# BeagleBoneBlack_cape_template.net
KiCad netlist of a schematic drawn in Altium Designer
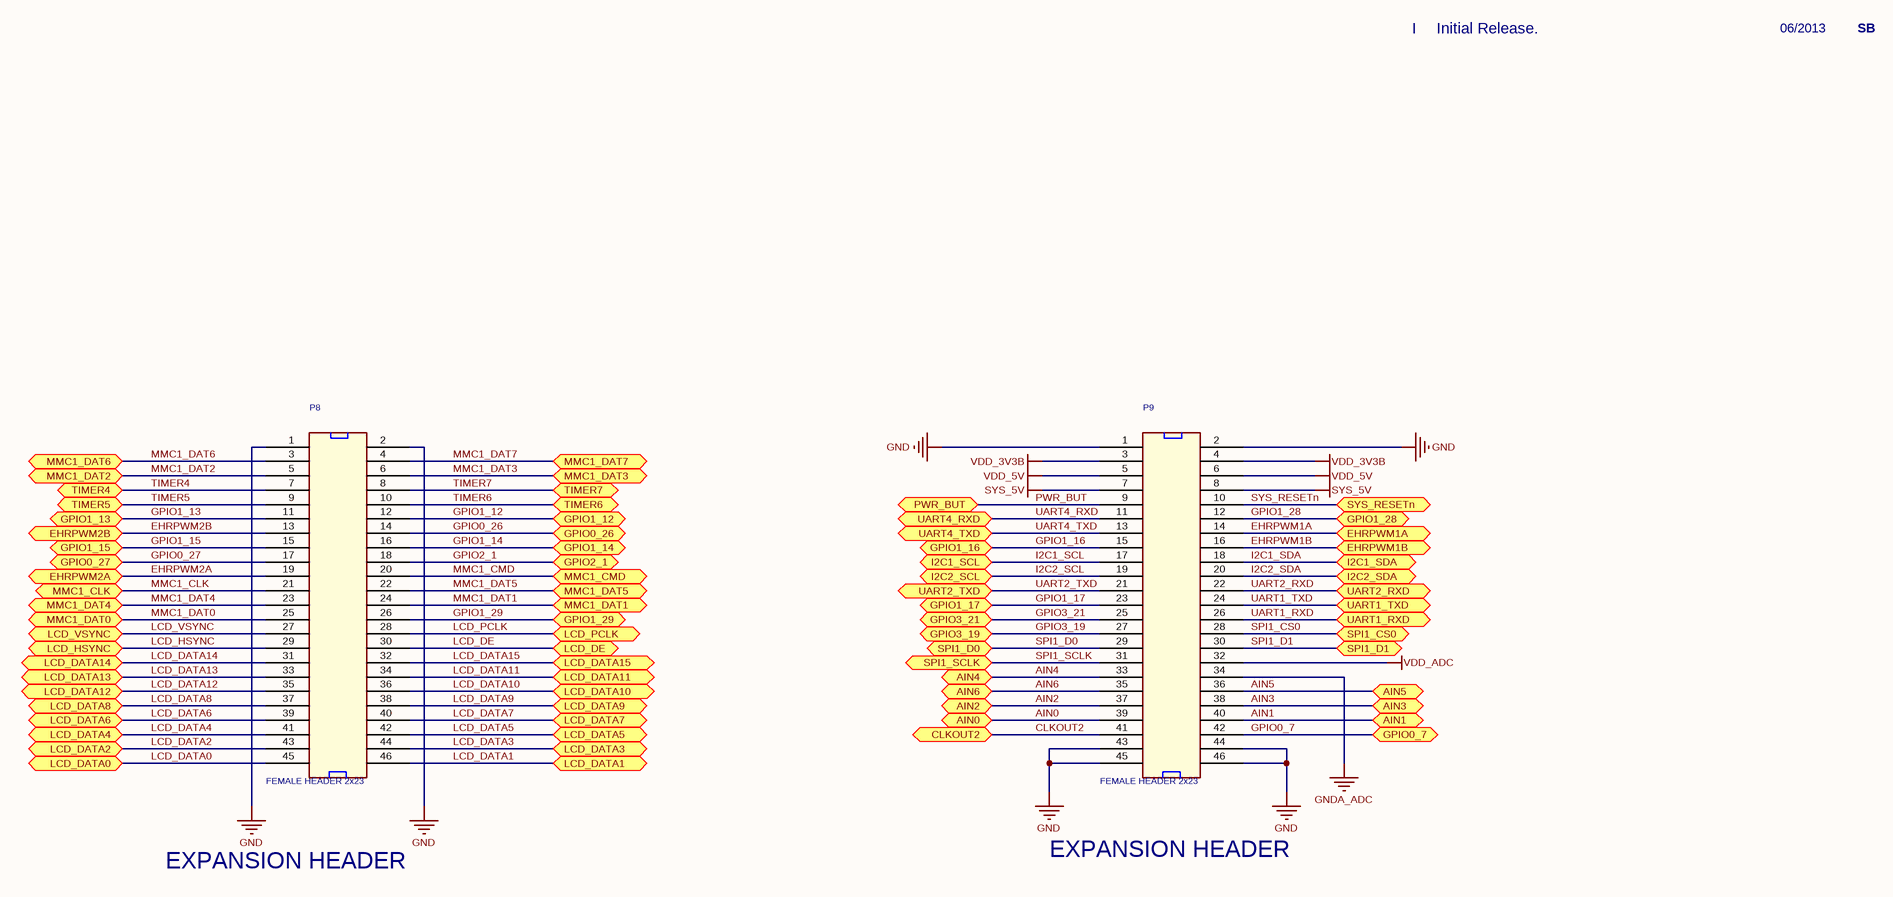
[diagram p0: BeagleBoneBlack_cape_template.SchDoc]

(export (version "E")
  (design (tool "Eeschema 10.0.6"))
  (components
    (comp (ref "P8")
      (value "FEMALE HEADER 2x23")
      (description "CONN HEADER FMAL 46PS.1\" DL GOLD")
      (fields
        (field (name "MANUFACTURER") "Sullins Connector Solutions")
        (field (name "MANUFACTURER PART NUMBER") "PPPC232LFBN-RC")
      )
      (libsource (lib "BEAGLEBONEBLACK_REV A5B") (part "HDR_46_F_2_0.1_0.1"))
    )
    (comp (ref "P9")
      (value "FEMALE HEADER 2x23")
      (description "CONN HEADER FMAL 46PS.1\" DL GOLD")
      (fields
        (field (name "MANUFACTURER") "Sullins Connector Solutions")
        (field (name "MANUFACTURER PART NUMBER") "PPPC232LFBN-RC")
      )
      (libsource (lib "BEAGLEBONEBLACK_REV A5B") (part "HDR_46_F_2_0.1_0.1"))
    )
  )
  (nets
    (net (code "1") (name "/AIN0") (class "Default")
      (node (ref "P9") (pin "39") (pinfunction "20_39") (pintype "passive"))
    )
    (net (code "2") (name "/AIN1") (class "Default")
      (node (ref "P9") (pin "40") (pinfunction "45_40") (pintype "passive"))
    )
    (net (code "3") (name "/AIN2") (class "Default")
      (node (ref "P9") (pin "37") (pinfunction "19_37") (pintype "passive"))
    )
    (net (code "4") (name "/AIN3") (class "Default")
      (node (ref "P9") (pin "38") (pinfunction "44_38") (pintype "passive"))
    )
    (net (code "5") (name "/AIN4") (class "Default")
      (node (ref "P9") (pin "33") (pinfunction "17_33") (pintype "passive"))
    )
    (net (code "6") (name "/AIN5") (class "Default")
      (node (ref "P9") (pin "36") (pinfunction "43_36") (pintype "passive"))
    )
    (net (code "7") (name "/AIN6") (class "Default")
      (node (ref "P9") (pin "35") (pinfunction "18_35") (pintype "passive"))
    )
    (net (code "8") (name "/CLKOUT2") (class "Default")
      (node (ref "P9") (pin "41") (pinfunction "21_41") (pintype "passive"))
    )
    (net (code "9") (name "/EHRPWM1A") (class "Default")
      (node (ref "P9") (pin "14") (pinfunction "32_14") (pintype "passive"))
    )
    (net (code "10") (name "/EHRPWM1B") (class "Default")
      (node (ref "P9") (pin "16") (pinfunction "33_16") (pintype "passive"))
    )
    (net (code "11") (name "/EHRPWM2A") (class "Default")
      (node (ref "P8") (pin "19") (pinfunction "10_19") (pintype "passive"))
    )
    (net (code "12") (name "/EHRPWM2B") (class "Default")
      (node (ref "P8") (pin "13") (pinfunction "7_13") (pintype "passive"))
    )
    (net (code "13") (name "/GPIO0_7") (class "Default")
      (node (ref "P9") (pin "42") (pinfunction "46_42") (pintype "passive"))
    )
    (net (code "14") (name "/GPIO0_26") (class "Default")
      (node (ref "P8") (pin "14") (pinfunction "32_14") (pintype "passive"))
    )
    (net (code "15") (name "/GPIO0_27") (class "Default")
      (node (ref "P8") (pin "17") (pinfunction "9_17") (pintype "passive"))
    )
    (net (code "16") (name "/GPIO1_12") (class "Default")
      (node (ref "P8") (pin "12") (pinfunction "31_12") (pintype "passive"))
    )
    (net (code "17") (name "/GPIO1_13") (class "Default")
      (node (ref "P8") (pin "11") (pinfunction "6_11") (pintype "passive"))
    )
    (net (code "18") (name "/GPIO1_14") (class "Default")
      (node (ref "P8") (pin "16") (pinfunction "33_16") (pintype "passive"))
    )
    (net (code "19") (name "/GPIO1_15") (class "Default")
      (node (ref "P8") (pin "15") (pinfunction "8_15") (pintype "passive"))
    )
    (net (code "20") (name "/GPIO1_16") (class "Default")
      (node (ref "P9") (pin "15") (pinfunction "8_15") (pintype "passive"))
    )
    (net (code "21") (name "/GPIO1_17") (class "Default")
      (node (ref "P9") (pin "23") (pinfunction "12_23") (pintype "passive"))
    )
    (net (code "22") (name "/GPIO1_28") (class "Default")
      (node (ref "P9") (pin "12") (pinfunction "31_12") (pintype "passive"))
    )
    (net (code "23") (name "/GPIO1_29") (class "Default")
      (node (ref "P8") (pin "26") (pinfunction "38_26") (pintype "passive"))
    )
    (net (code "24") (name "/GPIO2_1") (class "Default")
      (node (ref "P8") (pin "18") (pinfunction "34_18") (pintype "passive"))
    )
    (net (code "25") (name "/GPIO3_19") (class "Default")
      (node (ref "P9") (pin "27") (pinfunction "14_27") (pintype "passive"))
    )
    (net (code "26") (name "/GPIO3_21") (class "Default")
      (node (ref "P9") (pin "25") (pinfunction "13_25") (pintype "passive"))
    )
    (net (code "27") (name "/I2C1_SCL") (class "Default")
      (node (ref "P9") (pin "17") (pinfunction "9_17") (pintype "passive"))
    )
    (net (code "28") (name "/I2C1_SDA") (class "Default")
      (node (ref "P9") (pin "18") (pinfunction "34_18") (pintype "passive"))
    )
    (net (code "29") (name "/I2C2_SCL") (class "Default")
      (node (ref "P9") (pin "19") (pinfunction "10_19") (pintype "passive"))
    )
    (net (code "30") (name "/I2C2_SDA") (class "Default")
      (node (ref "P9") (pin "20") (pinfunction "35_20") (pintype "passive"))
    )
    (net (code "31") (name "/LCD_DATA0") (class "Default")
      (node (ref "P8") (pin "45") (pinfunction "23_45") (pintype "passive"))
    )
    (net (code "32") (name "/LCD_DATA1") (class "Default")
      (node (ref "P8") (pin "46") (pinfunction "48_46") (pintype "passive"))
    )
    (net (code "33") (name "/LCD_DATA2") (class "Default")
      (node (ref "P8") (pin "43") (pinfunction "22_43") (pintype "passive"))
    )
    (net (code "34") (name "/LCD_DATA3") (class "Default")
      (node (ref "P8") (pin "44") (pinfunction "47_44") (pintype "passive"))
    )
    (net (code "35") (name "/LCD_DATA4") (class "Default")
      (node (ref "P8") (pin "41") (pinfunction "21_41") (pintype "passive"))
    )
    (net (code "36") (name "/LCD_DATA5") (class "Default")
      (node (ref "P8") (pin "42") (pinfunction "46_42") (pintype "passive"))
    )
    (net (code "37") (name "/LCD_DATA6") (class "Default")
      (node (ref "P8") (pin "39") (pinfunction "20_39") (pintype "passive"))
    )
    (net (code "38") (name "/LCD_DATA7") (class "Default")
      (node (ref "P8") (pin "40") (pinfunction "45_40") (pintype "passive"))
    )
    (net (code "39") (name "/LCD_DATA8") (class "Default")
      (node (ref "P8") (pin "37") (pinfunction "19_37") (pintype "passive"))
    )
    (net (code "40") (name "/LCD_DATA9") (class "Default")
      (node (ref "P8") (pin "38") (pinfunction "44_38") (pintype "passive"))
    )
    (net (code "41") (name "/LCD_DATA10") (class "Default")
      (node (ref "P8") (pin "36") (pinfunction "43_36") (pintype "passive"))
    )
    (net (code "42") (name "/LCD_DATA11") (class "Default")
      (node (ref "P8") (pin "34") (pinfunction "42_34") (pintype "passive"))
    )
    (net (code "43") (name "/LCD_DATA12") (class "Default")
      (node (ref "P8") (pin "35") (pinfunction "18_35") (pintype "passive"))
    )
    (net (code "44") (name "/LCD_DATA13") (class "Default")
      (node (ref "P8") (pin "33") (pinfunction "17_33") (pintype "passive"))
    )
    (net (code "45") (name "/LCD_DATA14") (class "Default")
      (node (ref "P8") (pin "31") (pinfunction "16_31") (pintype "passive"))
    )
    (net (code "46") (name "/LCD_DATA15") (class "Default")
      (node (ref "P8") (pin "32") (pinfunction "41_32") (pintype "passive"))
    )
    (net (code "47") (name "/LCD_DE") (class "Default")
      (node (ref "P8") (pin "30") (pinfunction "40_30") (pintype "passive"))
    )
    (net (code "48") (name "/LCD_HSYNC") (class "Default")
      (node (ref "P8") (pin "29") (pinfunction "15_29") (pintype "passive"))
    )
    (net (code "49") (name "/LCD_PCLK") (class "Default")
      (node (ref "P8") (pin "28") (pinfunction "39_28") (pintype "passive"))
    )
    (net (code "50") (name "/LCD_VSYNC") (class "Default")
      (node (ref "P8") (pin "27") (pinfunction "14_27") (pintype "passive"))
    )
    (net (code "51") (name "/MMC1_CLK") (class "Default")
      (node (ref "P8") (pin "21") (pinfunction "11_21") (pintype "passive"))
    )
    (net (code "52") (name "/MMC1_CMD") (class "Default")
      (node (ref "P8") (pin "20") (pinfunction "35_20") (pintype "passive"))
    )
    (net (code "53") (name "/MMC1_DAT0") (class "Default")
      (node (ref "P8") (pin "25") (pinfunction "13_25") (pintype "passive"))
    )
    (net (code "54") (name "/MMC1_DAT1") (class "Default")
      (node (ref "P8") (pin "24") (pinfunction "37_24") (pintype "passive"))
    )
    (net (code "55") (name "/MMC1_DAT2") (class "Default")
      (node (ref "P8") (pin "5") (pinfunction "3_5") (pintype "passive"))
    )
    (net (code "56") (name "/MMC1_DAT3") (class "Default")
      (node (ref "P8") (pin "6") (pinfunction "28_6") (pintype "passive"))
    )
    (net (code "57") (name "/MMC1_DAT4") (class "Default")
      (node (ref "P8") (pin "23") (pinfunction "12_23") (pintype "passive"))
    )
    (net (code "58") (name "/MMC1_DAT5") (class "Default")
      (node (ref "P8") (pin "22") (pinfunction "36_22") (pintype "passive"))
    )
    (net (code "59") (name "/MMC1_DAT6") (class "Default")
      (node (ref "P8") (pin "3") (pinfunction "2_3") (pintype "passive"))
    )
    (net (code "60") (name "/MMC1_DAT7") (class "Default")
      (node (ref "P8") (pin "4") (pinfunction "27_4") (pintype "passive"))
    )
    (net (code "61") (name "/PWR_BUT") (class "Default")
      (node (ref "P9") (pin "9") (pinfunction "5_9") (pintype "passive"))
    )
    (net (code "62") (name "/SPI1_CS0") (class "Default")
      (node (ref "P9") (pin "28") (pinfunction "39_28") (pintype "passive"))
    )
    (net (code "63") (name "/SPI1_D0") (class "Default")
      (node (ref "P9") (pin "29") (pinfunction "15_29") (pintype "passive"))
    )
    (net (code "64") (name "/SPI1_D1") (class "Default")
      (node (ref "P9") (pin "30") (pinfunction "40_30") (pintype "passive"))
    )
    (net (code "65") (name "/SPI1_SCLK") (class "Default")
      (node (ref "P9") (pin "31") (pinfunction "16_31") (pintype "passive"))
    )
    (net (code "66") (name "/SYS_RESETn") (class "Default")
      (node (ref "P9") (pin "10") (pinfunction "30_10") (pintype "passive"))
    )
    (net (code "67") (name "/TIMER4") (class "Default")
      (node (ref "P8") (pin "7") (pinfunction "4_7") (pintype "passive"))
    )
    (net (code "68") (name "/TIMER5") (class "Default")
      (node (ref "P8") (pin "9") (pinfunction "5_9") (pintype "passive"))
    )
    (net (code "69") (name "/TIMER6") (class "Default")
      (node (ref "P8") (pin "10") (pinfunction "30_10") (pintype "passive"))
    )
    (net (code "70") (name "/TIMER7") (class "Default")
      (node (ref "P8") (pin "8") (pinfunction "29_8") (pintype "passive"))
    )
    (net (code "71") (name "/UART1_RXD") (class "Default")
      (node (ref "P9") (pin "26") (pinfunction "38_26") (pintype "passive"))
    )
    (net (code "72") (name "/UART1_TXD") (class "Default")
      (node (ref "P9") (pin "24") (pinfunction "37_24") (pintype "passive"))
    )
    (net (code "73") (name "/UART2_RXD") (class "Default")
      (node (ref "P9") (pin "22") (pinfunction "36_22") (pintype "passive"))
    )
    (net (code "74") (name "/UART2_TXD") (class "Default")
      (node (ref "P9") (pin "21") (pinfunction "11_21") (pintype "passive"))
    )
    (net (code "75") (name "/UART4_RXD") (class "Default")
      (node (ref "P9") (pin "11") (pinfunction "6_11") (pintype "passive"))
    )
    (net (code "76") (name "/UART4_TXD") (class "Default")
      (node (ref "P9") (pin "13") (pinfunction "7_13") (pintype "passive"))
    )
    (net (code "77") (name "GND") (class "Default")
      (node (ref "P8") (pin "1") (pinfunction "1_1") (pintype "passive"))
      (node (ref "P8") (pin "2") (pinfunction "26_2") (pintype "passive"))
      (node (ref "P9") (pin "1") (pinfunction "1_1") (pintype "passive"))
      (node (ref "P9") (pin "2") (pinfunction "26_2") (pintype "passive"))
      (node (ref "P9") (pin "43") (pinfunction "22_43") (pintype "passive"))
      (node (ref "P9") (pin "44") (pinfunction "47_44") (pintype "passive"))
      (node (ref "P9") (pin "45") (pinfunction "23_45") (pintype "passive"))
      (node (ref "P9") (pin "46") (pinfunction "48_46") (pintype "passive"))
    )
    (net (code "78") (name "GNDA_ADC") (class "Default")
      (node (ref "P9") (pin "34") (pinfunction "42_34") (pintype "passive"))
    )
    (net (code "79") (name "SYS_5V") (class "Default")
      (node (ref "P9") (pin "7") (pinfunction "4_7") (pintype "passive"))
      (node (ref "P9") (pin "8") (pinfunction "29_8") (pintype "passive"))
    )
    (net (code "80") (name "VDD_3V3B") (class "Default")
      (node (ref "P9") (pin "3") (pinfunction "2_3") (pintype "passive"))
      (node (ref "P9") (pin "4") (pinfunction "27_4") (pintype "passive"))
    )
    (net (code "81") (name "VDD_5V") (class "Default")
      (node (ref "P9") (pin "5") (pinfunction "3_5") (pintype "passive"))
      (node (ref "P9") (pin "6") (pinfunction "28_6") (pintype "passive"))
    )
    (net (code "82") (name "VDD_ADC") (class "Default")
      (node (ref "P9") (pin "32") (pinfunction "41_32") (pintype "passive"))
    )
  )
)
